# auto-discharge.net
KiCad netlist of a schematic drawn in Altium Designer
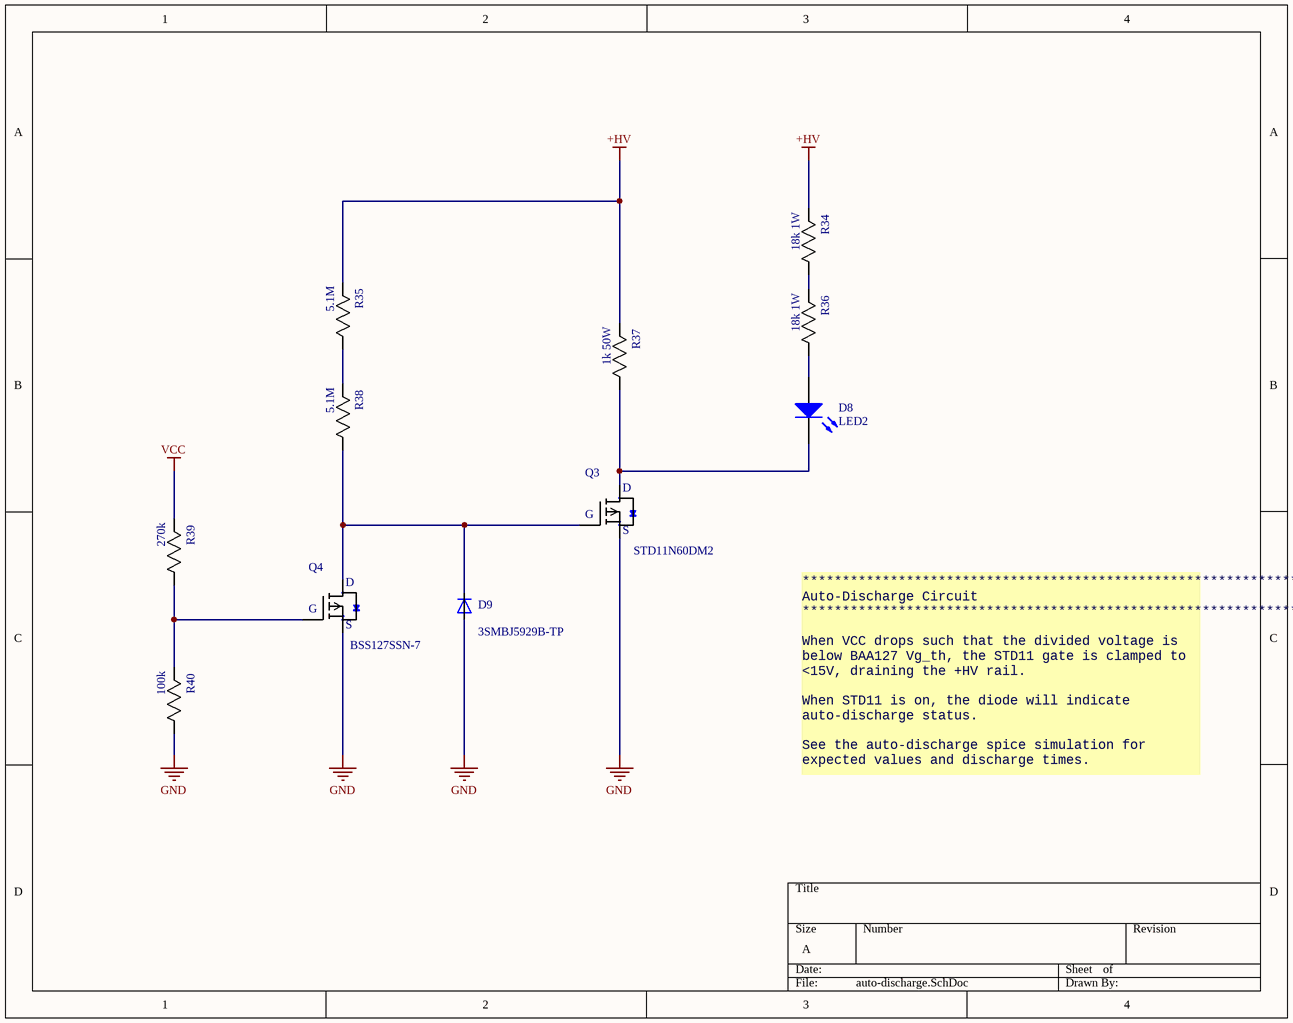
[diagram p0: auto-discharge.SchDoc]

(export (version "E")
  (design (tool "Eeschema 10.0.6"))
  (components
    (comp (ref "D8")
      (value "LED2")
      (footprint "3.2X1.6X1.1")
      (description "Typical RED, GREEN, YELLOW, AMBER GaAs LED")
      (libsource (lib "AltiumLibraries") (part "LED RED SMD"))
    )
    (comp (ref "D9")
      (value "3SMBJ5929B-TP")
      (footprint "DO-214AA")
      (description "Diode ZENER 15V 3W")
      (libsource (lib "AltiumLibraries") (part "DIODE ZENER 15V 3W"))
    )
    (comp (ref "Q3")
      (value "STD11N60DM2")
      (footprint "DPAK (TO-252)")
      (fields (field (name "MFG") "STMicroelectronics"))
      (libsource (lib "AltiumLibraries") (part "STD11N60DM2"))
    )
    (comp (ref "Q4")
      (value "BSS127SSN-7")
      (footprint "SOT-23 (3)")
      (description "Small Signal N-Ch, 600Vds")
      (fields (field (name "MFG") "Diodes Incorporated"))
      (libsource (lib "AltiumLibraries") (part "BSS127SSN-7"))
    )
    (comp (ref "R34")
      (value "18k 1W")
      (footprint "2512")
      (description "RES SMD 18K OHM 5% 1W 2512")
      (fields (field (name "TOLERANCE") "5%"))
      (libsource (lib "AltiumLibraries") (part "RES 18k 1W"))
    )
    (comp (ref "R35")
      (value "5.1M")
      (footprint "0805")
      (description "RES SMD 5.1 MOHM 5% 1/8W 0805")
      (fields (field (name "TOLERANCE") "5%"))
      (libsource (lib "") (part "RES 5.1M 1/8W-5%_1"))
    )
    (comp (ref "R36")
      (value "18k 1W")
      (footprint "2512")
      (description "RES SMD 18K OHM 5% 1W 2512")
      (fields (field (name "TOLERANCE") "5%"))
      (libsource (lib "AltiumLibraries") (part "RES 18k 1W"))
    )
    (comp (ref "R37")
      (value "1k 50W")
      (footprint "D2PAK (TO-263)")
      (description "RES SMD 1.5K OHM 1% 50W D2PAK")
      (fields (field (name "TOLERANCE") "1%"))
      (libsource (lib "AltiumLibraries") (part "RES 1.5k 50W"))
    )
    (comp (ref "R38")
      (value "5.1M")
      (footprint "0805")
      (description "RES SMD 5.1 MOHM 5% 1/8W 0805")
      (fields (field (name "TOLERANCE") "5%"))
      (libsource (lib "AltiumLibraries") (part "RES 5.1M 1/8W-5%"))
    )
    (comp (ref "R39")
      (value "270k")
      (footprint "0805")
      (description "RES SMD 270K OHM 5% 1/8W 0805")
      (fields (field (name "TOLERANCE") "5%"))
      (libsource (lib "AltiumLibraries") (part "RES 270k 1/8W"))
    )
    (comp (ref "R40")
      (value "100k")
      (footprint "0805")
      (description "RES SMD 100K OHM 1% 1/8W 0805")
      (fields (field (name "TOLERANCE") "1%"))
      (libsource (lib "AltiumLibraries") (part "RES 100k 1/8W - 1%"))
    )
  )
  (nets
    (net (code "1") (name "+HV") (class "Default")
      (node (ref "R34") (pin "2") (pinfunction "R2_2") (pintype "passive"))
      (node (ref "R35") (pin "2") (pinfunction "R2_2") (pintype "passive"))
      (node (ref "R37") (pin "2") (pinfunction "R2_2") (pintype "passive"))
    )
    (net (code "2") (name "GND") (class "Default")
      (node (ref "D9") (pin "A") (pinfunction "A_A") (pintype "passive"))
      (node (ref "Q3") (pin "S") (pinfunction "S_S") (pintype "passive"))
      (node (ref "Q4") (pin "S") (pinfunction "S_S") (pintype "passive"))
      (node (ref "R40") (pin "1") (pinfunction "R1_1") (pintype "passive"))
    )
    (net (code "3") (name "Net-(D8-A)") (class "Default")
      (node (ref "D8") (pin "1") (pinfunction "A_1") (pintype "passive"))
      (node (ref "R36") (pin "1") (pinfunction "R1_1") (pintype "passive"))
    )
    (net (code "4") (name "Net-(D8-K)") (class "Default")
      (node (ref "D8") (pin "2") (pinfunction "K_2") (pintype "passive"))
      (node (ref "Q3") (pin "D") (pinfunction "D_D") (pintype "passive"))
      (node (ref "R37") (pin "1") (pinfunction "R1_1") (pintype "passive"))
    )
    (net (code "5") (name "Net-(R34-R1)") (class "Default")
      (node (ref "R34") (pin "1") (pinfunction "R1_1") (pintype "passive"))
      (node (ref "R36") (pin "2") (pinfunction "R2_2") (pintype "passive"))
    )
    (net (code "6") (name "Net-(R35-R1)") (class "Default")
      (node (ref "R35") (pin "1") (pinfunction "R1_1") (pintype "passive"))
      (node (ref "R38") (pin "2") (pinfunction "R2_2") (pintype "passive"))
    )
    (net (code "7") (name "Net-(R38-R1)") (class "Default")
      (node (ref "D9") (pin "C") (pinfunction "C_C") (pintype "passive"))
      (node (ref "Q3") (pin "G") (pinfunction "G_G") (pintype "passive"))
      (node (ref "Q4") (pin "D") (pinfunction "D_D") (pintype "passive"))
      (node (ref "R38") (pin "1") (pinfunction "R1_1") (pintype "passive"))
    )
    (net (code "8") (name "Net-(R39-R1)") (class "Default")
      (node (ref "Q4") (pin "G") (pinfunction "G_G") (pintype "passive"))
      (node (ref "R39") (pin "1") (pinfunction "R1_1") (pintype "passive"))
      (node (ref "R40") (pin "2") (pinfunction "R2_2") (pintype "passive"))
    )
    (net (code "9") (name "VCC") (class "Default")
      (node (ref "R39") (pin "2") (pinfunction "R2_2") (pintype "passive"))
    )
  )
)
